# Quectel_M66.net
KiCad netlist of a schematic drawn in Altium Designer
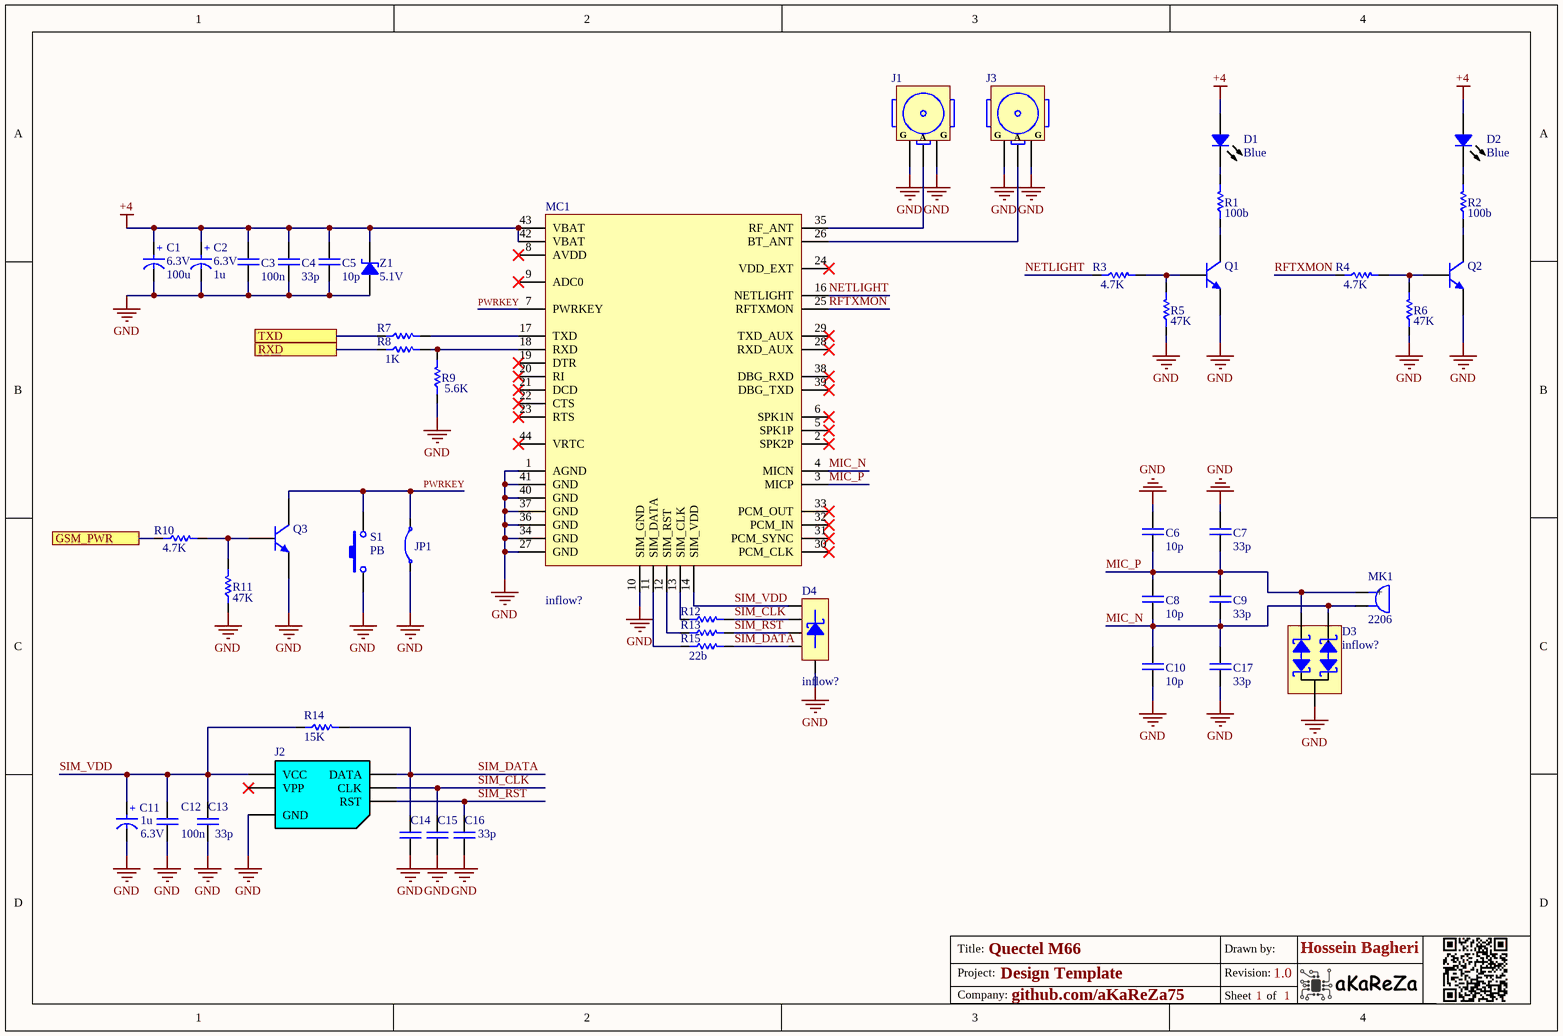
[diagram p0: Quectel M66.SchDoc]

(export (version "E")
  (design (tool "Eeschema 10.0.6"))
  (components
    (comp (ref "C1")
      (value "100u")
      (footprint "SMT_C_Tantalum_C")
      (description "Tantalum Capacitor,TAJ Series-SMD")
      (fields (field (name "RATING") "6.3V"))
      (libsource (lib "aKaReZa") (part "Cap_Tantalum"))
    )
    (comp (ref "C2")
      (value "1u")
      (footprint "SMT_C_Tantalum_A")
      (description "Tantalum Capacitor,TAJ Series-SMD")
      (fields (field (name "RATING") "6.3V"))
      (libsource (lib "aKaReZa") (part "Cap_Tantalum"))
    )
    (comp (ref "C3")
      (value "100n")
      (footprint "CAP 1206/3216")
      (description "Bipolar ceramic capacitor SMD")
      (libsource (lib "aKaReZa") (part "Cap_Multi_SMD_100nF_1206"))
    )
    (comp (ref "C4")
      (value "33p")
      (footprint "CAP 1206/3216")
      (description "Bipolar ceramic capacitor SMD")
      (libsource (lib "aKaReZa") (part "Cap_Multi_SMD_1206"))
    )
    (comp (ref "C5")
      (value "10p")
      (footprint "CAP 1206/3216")
      (description "Bipolar ceramic capacitor SMD")
      (libsource (lib "aKaReZa") (part "Cap_Multi_SMD_1206"))
    )
    (comp (ref "C6")
      (value "10p")
      (footprint "CAP 0603/1608")
      (description "Bipolar ceramic capacitor SMD")
      (fields (field (name "VALIDATION") "Valid"))
      (libsource (lib "aKaReZa") (part "Cap_Multi_SMD"))
    )
    (comp (ref "C7")
      (value "33p")
      (footprint "CAP 0603/1608")
      (description "Bipolar ceramic capacitor SMD")
      (fields (field (name "VALIDATION") "Valid"))
      (libsource (lib "aKaReZa") (part "Cap_Multi_SMD"))
    )
    (comp (ref "C8")
      (value "10p")
      (footprint "CAP 0603/1608")
      (description "Bipolar ceramic capacitor SMD")
      (fields (field (name "VALIDATION") "Valid"))
      (libsource (lib "aKaReZa") (part "Cap_Multi_SMD"))
    )
    (comp (ref "C9")
      (value "33p")
      (footprint "CAP 0603/1608")
      (description "Bipolar ceramic capacitor SMD")
      (fields (field (name "VALIDATION") "Valid"))
      (libsource (lib "aKaReZa") (part "Cap_Multi_SMD"))
    )
    (comp (ref "C10")
      (value "10p")
      (footprint "CAP 0603/1608")
      (description "Bipolar ceramic capacitor SMD")
      (fields (field (name "VALIDATION") "Valid"))
      (libsource (lib "aKaReZa") (part "Cap_Multi_SMD"))
    )
    (comp (ref "C11")
      (value "1u")
      (footprint "SMT_C_Tantalum_A")
      (description "Tantalum Capacitor,TAJ Series-SMD")
      (fields (field (name "RATING") "6.3V"))
      (libsource (lib "aKaReZa") (part "Cap_Tantalum"))
    )
    (comp (ref "C12")
      (value "100n")
      (footprint "CAP 0805/2012")
      (description "Bipolar ceramic capacitor SMD")
      (libsource (lib "aKaReZa") (part "Cap_Multi_SMD_100nF_0805"))
    )
    (comp (ref "C13")
      (value "33p")
      (footprint "CAP 0805/2012")
      (description "Bipolar ceramic capacitor SMD")
      (libsource (lib "aKaReZa") (part "Cap_Multi_SMD_0805"))
    )
    (comp (ref "C14")
      (value "33p")
      (footprint "CAP 0805/2012")
      (description "Bipolar ceramic capacitor SMD")
      (libsource (lib "aKaReZa") (part "Cap_Multi_SMD_0805"))
    )
    (comp (ref "C15")
      (value "33p")
      (footprint "CAP 0805/2012")
      (description "Bipolar ceramic capacitor SMD")
      (libsource (lib "aKaReZa") (part "Cap_Multi_SMD_0805"))
    )
    (comp (ref "C16")
      (value "33p")
      (footprint "CAP 0805/2012")
      (description "Bipolar ceramic capacitor SMD")
      (libsource (lib "aKaReZa") (part "Cap_Multi_SMD_0805"))
    )
    (comp (ref "C17")
      (value "33p")
      (footprint "CAP 0603/1608")
      (description "Bipolar ceramic capacitor SMD")
      (fields (field (name "VALIDATION") "Valid"))
      (libsource (lib "aKaReZa") (part "Cap_Multi_SMD"))
    )
    (comp (ref "D1")
      (value "Blue")
      (footprint "LED 0805/2012 BLUE")
      (description "LED")
      (fields (field (name "VALIDATION") "Valid"))
      (libsource (lib "aKaReZa") (part "Semi_LED_SMD"))
    )
    (comp (ref "D2")
      (value "Blue")
      (footprint "LED 0805/2012 BLUE")
      (description "LED")
      (fields (field (name "VALIDATION") "Valid"))
      (libsource (lib "aKaReZa") (part "Semi_LED_SMD"))
    )
    (comp (ref "D3")
      (value "SM712")
      (footprint "SOT23_M")
      (description "TVS, ESD PROTECT, 2CH, 400W/17A PP, 7.5VBR, ±8KV ESDmin")
      (fields (field (name "INFLOW") "inflow?") (field (name "VALIDATION") "Valid"))
      (libsource (lib "aKaReZa") (part "Semi_Diod_TVS_SM712"))
    )
    (comp (ref "D4")
      (value "SMF-05")
      (footprint "SC70-5_N")
      (description "TVS Diode Array")
      (fields (field (name "INFLOW") "inflow?") (field (name "VALIDATION") "Valid"))
      (libsource (lib "aKaReZa") (part "Semi_Diod_TVS_SMF05"))
    )
    (comp (ref "J1") (value "U.FL") (footprint "IPEX-3x3mm") (libsource (lib "aKaReZa") (part "Con_RF_U.FL")))
    (comp (ref "J2")
      (value "6'Pin")
      (footprint "GCT_SIM8051_Plastik")
      (description "Nano SimCard Holder 6P")
      (fields (field (name "VALIDATION") "Valid"))
      (libsource (lib "aKaReZa") (part "Con_Socket_SimCard_1"))
    )
    (comp (ref "J3") (value "U.FL") (footprint "IPEX-3x3mm") (libsource (lib "aKaReZa") (part "Con_RF_U.FL")))
    (comp (ref "JP1")
      (value "Jumper")
      (footprint "RESC2012M (0805)")
      (description "Jumper Component")
      (fields (field (name "VALIDATION") "Valid"))
      (libsource (lib "aKaReZa") (part "Other_Elec_Jumper_0805"))
    )
    (comp (ref "MC1")
      (value "M66")
      (footprint "m66")
      (description "Quectel GSM/GPRS Module")
      (fields (field (name "INFLOW") "inflow?") (field (name "VALIDATION") "Valid"))
      (libsource (lib "aKaReZa") (part "ModSen_Com_M66"))
    )
    (comp (ref "MK1")
      (value "Mic")
      (footprint "mic6")
      (description "Microphone")
      (fields (field (name "INFLOW") "2206") (field (name "VALIDATION") "NT"))
      (libsource (lib "aKaReZa") (part "Other_Elec_Microphone"))
    )
    (comp (ref "Q1")
      (value "NPN")
      (footprint "SOT23_N")
      (description "NPN General purpose Transistor")
      (fields (field (name "VALIDATION") "Valid"))
      (libsource (lib "aKaReZa") (part "Semi_BJT_BC817"))
    )
    (comp (ref "Q2")
      (value "NPN")
      (footprint "SOT23_N")
      (description "NPN General purpose Transistor")
      (fields (field (name "VALIDATION") "Valid"))
      (libsource (lib "aKaReZa") (part "Semi_BJT_BC817"))
    )
    (comp (ref "Q3")
      (value "NPN")
      (footprint "SOT23_N")
      (description "NPN General purpose Transistor")
      (fields (field (name "VALIDATION") "Valid"))
      (libsource (lib "aKaReZa") (part "Semi_BJT_BC817"))
    )
    (comp (ref "R1")
      (value "100b")
      (footprint "RES 0805 (2012X06L)")
      (description "Resistor")
      (libsource (lib "aKaReZa") (part "Res_SMD_0805"))
    )
    (comp (ref "R2")
      (value "100b")
      (footprint "RES 0805 (2012X06L)")
      (description "Resistor")
      (libsource (lib "aKaReZa") (part "Res_SMD_0805"))
    )
    (comp (ref "R3")
      (value "4.7K")
      (footprint "RES 0805 (2012X06L)")
      (description "Resistor")
      (libsource (lib "aKaReZa") (part "Res_SMD_0805"))
    )
    (comp (ref "R4")
      (value "4.7K")
      (footprint "RES 0805 (2012X06L)")
      (description "Resistor")
      (libsource (lib "aKaReZa") (part "Res_SMD_0805"))
    )
    (comp (ref "R5")
      (value "47K")
      (footprint "RES 0805 (2012X06L)")
      (description "Resistor")
      (libsource (lib "aKaReZa") (part "Res_SMD_0805"))
    )
    (comp (ref "R6")
      (value "47K")
      (footprint "RES 0805 (2012X06L)")
      (description "Resistor")
      (libsource (lib "aKaReZa") (part "Res_SMD_0805"))
    )
    (comp (ref "R7")
      (value "1K")
      (footprint "RES 0805 (2012X06L)")
      (description "Resistor")
      (libsource (lib "aKaReZa") (part "Res_SMD_0805"))
    )
    (comp (ref "R8")
      (value "1K")
      (footprint "RES 0805 (2012X06L)")
      (description "Resistor")
      (libsource (lib "aKaReZa") (part "Res_SMD_0805"))
    )
    (comp (ref "R9")
      (value "5.6K")
      (footprint "RES 0805 (2012X06L)")
      (description "Resistor")
      (libsource (lib "aKaReZa") (part "Res_SMD_0805"))
    )
    (comp (ref "R10")
      (value "4.7K")
      (footprint "RES 0805 (2012X06L)")
      (description "Resistor")
      (libsource (lib "aKaReZa") (part "Res_SMD_0805"))
    )
    (comp (ref "R11")
      (value "47K")
      (footprint "RES 0805 (2012X06L)")
      (description "Resistor")
      (libsource (lib "aKaReZa") (part "Res_SMD_0805"))
    )
    (comp (ref "R12")
      (value "22b")
      (footprint "RES 0805 (2012X06L)")
      (description "Resistor")
      (libsource (lib "aKaReZa") (part "Res_SMD_0805"))
    )
    (comp (ref "R13")
      (value "22b")
      (footprint "RES 0805 (2012X06L)")
      (description "Resistor")
      (libsource (lib "aKaReZa") (part "Res_SMD_0805"))
    )
    (comp (ref "R14")
      (value "15K")
      (footprint "RES 0805 (2012X06L)")
      (description "Resistor")
      (libsource (lib "aKaReZa") (part "Res_SMD_0805"))
    )
    (comp (ref "R15")
      (value "22b")
      (footprint "RES 0805 (2012X06L)")
      (description "Resistor")
      (libsource (lib "aKaReZa") (part "Res_SMD_0805"))
    )
    (comp (ref "S1")
      (value "PB")
      (footprint "SW_PB_SMD_2PIN_SPST_6X3X2")
      (description "SMT Tactile ‎Switch")
      (fields (field (name "VALIDATION") "Valid"))
      (libsource (lib "aKaReZa") (part "SW_PushButton_2_SMD"))
    )
    (comp (ref "Z1")
      (value "5.1V")
      (footprint "SOD80, LL-34")
      (description "Zener Diode")
      (libsource (lib "aKaReZa") (part "Semi_Diod_Zener_SMD"))
    )
  )
  (nets
    (net (code "1") (name "+4") (class "Default")
      (node (ref "C1") (pin "1") (pinfunction "+_1") (pintype "passive"))
      (node (ref "C2") (pin "1") (pinfunction "+_1") (pintype "passive"))
      (node (ref "C3") (pin "1") (pinfunction "1_1") (pintype "passive"))
      (node (ref "C4") (pin "1") (pinfunction "1_1") (pintype "passive"))
      (node (ref "C5") (pin "1") (pinfunction "1_1") (pintype "passive"))
      (node (ref "D1") (pin "1") (pinfunction "1_1") (pintype "passive"))
      (node (ref "D2") (pin "1") (pinfunction "1_1") (pintype "passive"))
      (node (ref "MC1") (pin "42") (pinfunction "VBAT_42") (pintype "passive"))
      (node (ref "MC1") (pin "43") (pinfunction "VBAT_43") (pintype "passive"))
      (node (ref "Z1") (pin "2") (pinfunction "2_2") (pintype "passive"))
    )
    (net (code "2") (name "/GSM_PWR") (class "Default")
      (node (ref "R10") (pin "1") (pinfunction "1_1") (pintype "passive"))
    )
    (net (code "3") (name "/MIC_N") (class "Default")
      (node (ref "C10") (pin "1") (pinfunction "1_1") (pintype "passive"))
      (node (ref "C17") (pin "1") (pinfunction "1_1") (pintype "passive"))
      (node (ref "C8") (pin "2") (pinfunction "2_2") (pintype "passive"))
      (node (ref "C9") (pin "2") (pinfunction "2_2") (pintype "passive"))
      (node (ref "D3") (pin "2") (pinfunction "2_2") (pintype "passive"))
      (node (ref "MC1") (pin "4") (pinfunction "MICN_4") (pintype "passive"))
      (node (ref "MK1") (pin "2") (pinfunction "2_2") (pintype "passive"))
    )
    (net (code "4") (name "/MIC_P") (class "Default")
      (node (ref "C6") (pin "2") (pinfunction "2_2") (pintype "passive"))
      (node (ref "C7") (pin "2") (pinfunction "2_2") (pintype "passive"))
      (node (ref "C8") (pin "1") (pinfunction "1_1") (pintype "passive"))
      (node (ref "C9") (pin "1") (pinfunction "1_1") (pintype "passive"))
      (node (ref "D3") (pin "1") (pinfunction "1_1") (pintype "passive"))
      (node (ref "MC1") (pin "3") (pinfunction "MICP_3") (pintype "passive"))
      (node (ref "MK1") (pin "1") (pinfunction "+_1") (pintype "passive"))
    )
    (net (code "5") (name "/NETLIGHT") (class "Default")
      (node (ref "MC1") (pin "16") (pinfunction "NETLIGHT_16") (pintype "passive"))
      (node (ref "R3") (pin "1") (pinfunction "1_1") (pintype "passive"))
    )
    (net (code "6") (name "/PWRKEY") (class "Default")
      (node (ref "JP1") (pin "2") (pinfunction "2_2") (pintype "passive"))
      (node (ref "MC1") (pin "7") (pinfunction "PWRKEY_7") (pintype "passive"))
      (node (ref "Q3") (pin "3") (pinfunction "C_3") (pintype "passive"))
      (node (ref "S1") (pin "2") (pinfunction "2_2") (pintype "passive"))
    )
    (net (code "7") (name "/RFTXMON") (class "Default")
      (node (ref "MC1") (pin "25") (pinfunction "RFTXMON_25") (pintype "passive"))
      (node (ref "R4") (pin "1") (pinfunction "1_1") (pintype "passive"))
    )
    (net (code "8") (name "/RXD") (class "Default")
      (node (ref "R8") (pin "1") (pinfunction "1_1") (pintype "passive"))
    )
    (net (code "9") (name "/SIM_CLK") (class "Default")
      (node (ref "C15") (pin "1") (pinfunction "1_1") (pintype "passive"))
      (node (ref "D4") (pin "4") (pinfunction "K_4") (pintype "passive"))
      (node (ref "J2") (pin "3") (pinfunction "CLK_3") (pintype "passive"))
      (node (ref "R12") (pin "2") (pinfunction "2_2") (pintype "passive"))
    )
    (net (code "10") (name "/SIM_DATA") (class "Default")
      (node (ref "C14") (pin "1") (pinfunction "1_1") (pintype "passive"))
      (node (ref "D4") (pin "5") (pinfunction "K_5") (pintype "passive"))
      (node (ref "J2") (pin "4") (pinfunction "DATA_4") (pintype "passive"))
      (node (ref "R14") (pin "2") (pinfunction "2_2") (pintype "passive"))
      (node (ref "R15") (pin "2") (pinfunction "2_2") (pintype "passive"))
    )
    (net (code "11") (name "/SIM_RST") (class "Default")
      (node (ref "C16") (pin "1") (pinfunction "1_1") (pintype "passive"))
      (node (ref "D4") (pin "1") (pinfunction "K_1") (pintype "passive"))
      (node (ref "J2") (pin "2") (pinfunction "RST_2") (pintype "passive"))
      (node (ref "R13") (pin "2") (pinfunction "2_2") (pintype "passive"))
    )
    (net (code "12") (name "/SIM_VDD") (class "Default")
      (node (ref "C11") (pin "1") (pinfunction "+_1") (pintype "passive"))
      (node (ref "C12") (pin "1") (pinfunction "1_1") (pintype "passive"))
      (node (ref "C13") (pin "1") (pinfunction "1_1") (pintype "passive"))
      (node (ref "D4") (pin "3") (pinfunction "K_3") (pintype "passive"))
      (node (ref "J2") (pin "1") (pinfunction "VCC_1") (pintype "passive"))
      (node (ref "MC1") (pin "14") (pinfunction "SIM_VDD_14") (pintype "passive"))
      (node (ref "R14") (pin "1") (pinfunction "1_1") (pintype "passive"))
    )
    (net (code "13") (name "/TXD") (class "Default")
      (node (ref "R7") (pin "1") (pinfunction "1_1") (pintype "passive"))
    )
    (net (code "14") (name "GND") (class "Default")
      (node (ref "C1") (pin "2") (pinfunction "-_2") (pintype "passive"))
      (node (ref "C10") (pin "2") (pinfunction "2_2") (pintype "passive"))
      (node (ref "C11") (pin "2") (pinfunction "-_2") (pintype "passive"))
      (node (ref "C12") (pin "2") (pinfunction "2_2") (pintype "passive"))
      (node (ref "C13") (pin "2") (pinfunction "2_2") (pintype "passive"))
      (node (ref "C14") (pin "2") (pinfunction "2_2") (pintype "passive"))
      (node (ref "C15") (pin "2") (pinfunction "2_2") (pintype "passive"))
      (node (ref "C16") (pin "2") (pinfunction "2_2") (pintype "passive"))
      (node (ref "C17") (pin "2") (pinfunction "2_2") (pintype "passive"))
      (node (ref "C2") (pin "2") (pinfunction "-_2") (pintype "passive"))
      (node (ref "C3") (pin "2") (pinfunction "2_2") (pintype "passive"))
      (node (ref "C4") (pin "2") (pinfunction "2_2") (pintype "passive"))
      (node (ref "C5") (pin "2") (pinfunction "2_2") (pintype "passive"))
      (node (ref "C6") (pin "1") (pinfunction "1_1") (pintype "passive"))
      (node (ref "C7") (pin "1") (pinfunction "1_1") (pintype "passive"))
      (node (ref "D3") (pin "3") (pinfunction "3_3") (pintype "passive"))
      (node (ref "D4") (pin "2") (pinfunction "K_2") (pintype "passive"))
      (node (ref "J1") (pin "2") (pinfunction "G_2") (pintype "passive"))
      (node (ref "J1") (pin "3") (pinfunction "G_3") (pintype "passive"))
      (node (ref "J2") (pin "5") (pinfunction "GND_5") (pintype "passive"))
      (node (ref "J3") (pin "2") (pinfunction "G_2") (pintype "passive"))
      (node (ref "J3") (pin "3") (pinfunction "G_3") (pintype "passive"))
      (node (ref "JP1") (pin "1") (pinfunction "1_1") (pintype "passive"))
      (node (ref "MC1") (pin "1") (pinfunction "AGND_1") (pintype "passive"))
      (node (ref "MC1") (pin "10") (pinfunction "SIM_GND_10") (pintype "passive"))
      (node (ref "MC1") (pin "27") (pinfunction "GND_27") (pintype "passive"))
      (node (ref "MC1") (pin "34") (pinfunction "GND_34") (pintype "passive"))
      (node (ref "MC1") (pin "36") (pinfunction "GND_36") (pintype "passive"))
      (node (ref "MC1") (pin "37") (pinfunction "GND_37") (pintype "passive"))
      (node (ref "MC1") (pin "40") (pinfunction "GND_40") (pintype "passive"))
      (node (ref "MC1") (pin "41") (pinfunction "GND_41") (pintype "passive"))
      (node (ref "Q1") (pin "2") (pinfunction "E_2") (pintype "passive"))
      (node (ref "Q2") (pin "2") (pinfunction "E_2") (pintype "passive"))
      (node (ref "Q3") (pin "2") (pinfunction "E_2") (pintype "passive"))
      (node (ref "R11") (pin "1") (pinfunction "1_1") (pintype "passive"))
      (node (ref "R5") (pin "1") (pinfunction "1_1") (pintype "passive"))
      (node (ref "R6") (pin "1") (pinfunction "1_1") (pintype "passive"))
      (node (ref "R9") (pin "1") (pinfunction "1_1") (pintype "passive"))
      (node (ref "S1") (pin "1") (pinfunction "1_1") (pintype "passive"))
      (node (ref "Z1") (pin "1") (pinfunction "1_1") (pintype "passive"))
    )
    (net (code "15") (name "Net-(D1-Pad2)") (class "Default")
      (node (ref "D1") (pin "2") (pinfunction "2_2") (pintype "passive"))
      (node (ref "R1") (pin "2") (pinfunction "2_2") (pintype "passive"))
    )
    (net (code "16") (name "Net-(D2-Pad2)") (class "Default")
      (node (ref "D2") (pin "2") (pinfunction "2_2") (pintype "passive"))
      (node (ref "R2") (pin "2") (pinfunction "2_2") (pintype "passive"))
    )
    (net (code "17") (name "Net-(J1-A)") (class "Default")
      (node (ref "J1") (pin "1") (pinfunction "A_1") (pintype "passive"))
      (node (ref "MC1") (pin "35") (pinfunction "RF_ANT_35") (pintype "passive"))
    )
    (net (code "18") (name "Net-(J3-A)") (class "Default")
      (node (ref "J3") (pin "1") (pinfunction "A_1") (pintype "passive"))
      (node (ref "MC1") (pin "26") (pinfunction "BT_ANT_26") (pintype "passive"))
    )
    (net (code "19") (name "Net-(MC1-RXD)") (class "Default")
      (node (ref "MC1") (pin "18") (pinfunction "RXD_18") (pintype "passive"))
      (node (ref "R8") (pin "2") (pinfunction "2_2") (pintype "passive"))
      (node (ref "R9") (pin "2") (pinfunction "2_2") (pintype "passive"))
    )
    (net (code "20") (name "Net-(MC1-SIM_CLK)") (class "Default")
      (node (ref "MC1") (pin "13") (pinfunction "SIM_CLK_13") (pintype "passive"))
      (node (ref "R12") (pin "1") (pinfunction "1_1") (pintype "passive"))
    )
    (net (code "21") (name "Net-(MC1-SIM_DATA)") (class "Default")
      (node (ref "MC1") (pin "11") (pinfunction "SIM_DATA_11") (pintype "passive"))
      (node (ref "R15") (pin "1") (pinfunction "1_1") (pintype "passive"))
    )
    (net (code "22") (name "Net-(MC1-SIM_RST)") (class "Default")
      (node (ref "MC1") (pin "12") (pinfunction "SIM_RST_12") (pintype "passive"))
      (node (ref "R13") (pin "1") (pinfunction "1_1") (pintype "passive"))
    )
    (net (code "23") (name "Net-(MC1-TXD)") (class "Default")
      (node (ref "MC1") (pin "17") (pinfunction "TXD_17") (pintype "passive"))
      (node (ref "R7") (pin "2") (pinfunction "2_2") (pintype "passive"))
    )
    (net (code "24") (name "Net-(Q1-B)") (class "Default")
      (node (ref "Q1") (pin "1") (pinfunction "B_1") (pintype "passive"))
      (node (ref "R3") (pin "2") (pinfunction "2_2") (pintype "passive"))
      (node (ref "R5") (pin "2") (pinfunction "2_2") (pintype "passive"))
    )
    (net (code "25") (name "Net-(Q1-C)") (class "Default")
      (node (ref "Q1") (pin "3") (pinfunction "C_3") (pintype "passive"))
      (node (ref "R1") (pin "1") (pinfunction "1_1") (pintype "passive"))
    )
    (net (code "26") (name "Net-(Q2-B)") (class "Default")
      (node (ref "Q2") (pin "1") (pinfunction "B_1") (pintype "passive"))
      (node (ref "R4") (pin "2") (pinfunction "2_2") (pintype "passive"))
      (node (ref "R6") (pin "2") (pinfunction "2_2") (pintype "passive"))
    )
    (net (code "27") (name "Net-(Q2-C)") (class "Default")
      (node (ref "Q2") (pin "3") (pinfunction "C_3") (pintype "passive"))
      (node (ref "R2") (pin "1") (pinfunction "1_1") (pintype "passive"))
    )
    (net (code "28") (name "Net-(Q3-B)") (class "Default")
      (node (ref "Q3") (pin "1") (pinfunction "B_1") (pintype "passive"))
      (node (ref "R10") (pin "2") (pinfunction "2_2") (pintype "passive"))
      (node (ref "R11") (pin "2") (pinfunction "2_2") (pintype "passive"))
    )
    (net (code "29") (name "unconnected-(J2-VPP-Pad6)") (class "Default")
      (node (ref "J2") (pin "6") (pinfunction "VPP_6") (pintype "passive+no_connect"))
    )
    (net (code "30") (name "unconnected-(MC1-ADC0-Pad9)") (class "Default")
      (node (ref "MC1") (pin "9") (pinfunction "ADC0_9") (pintype "passive+no_connect"))
    )
    (net (code "31") (name "unconnected-(MC1-AVDD-Pad8)") (class "Default")
      (node (ref "MC1") (pin "8") (pinfunction "AVDD_8") (pintype "passive+no_connect"))
    )
    (net (code "32") (name "unconnected-(MC1-CTS-Pad22)") (class "Default")
      (node (ref "MC1") (pin "22") (pinfunction "CTS_22") (pintype "passive+no_connect"))
    )
    (net (code "33") (name "unconnected-(MC1-DBG_RXD-Pad38)") (class "Default")
      (node (ref "MC1") (pin "38") (pinfunction "DBG_RXD_38") (pintype "passive+no_connect"))
    )
    (net (code "34") (name "unconnected-(MC1-DBG_TXD-Pad39)") (class "Default")
      (node (ref "MC1") (pin "39") (pinfunction "DBG_TXD_39") (pintype "passive+no_connect"))
    )
    (net (code "35") (name "unconnected-(MC1-DCD-Pad21)") (class "Default")
      (node (ref "MC1") (pin "21") (pinfunction "DCD_21") (pintype "passive+no_connect"))
    )
    (net (code "36") (name "unconnected-(MC1-DTR-Pad19)") (class "Default")
      (node (ref "MC1") (pin "19") (pinfunction "DTR_19") (pintype "passive+no_connect"))
    )
    (net (code "37") (name "unconnected-(MC1-PCM_CLK-Pad30)") (class "Default")
      (node (ref "MC1") (pin "30") (pinfunction "PCM_CLK_30") (pintype "passive+no_connect"))
    )
    (net (code "38") (name "unconnected-(MC1-PCM_IN-Pad32)") (class "Default")
      (node (ref "MC1") (pin "32") (pinfunction "PCM_IN_32") (pintype "passive+no_connect"))
    )
    (net (code "39") (name "unconnected-(MC1-PCM_OUT-Pad33)") (class "Default")
      (node (ref "MC1") (pin "33") (pinfunction "PCM_OUT_33") (pintype "passive+no_connect"))
    )
    (net (code "40") (name "unconnected-(MC1-PCM_SYNC-Pad31)") (class "Default")
      (node (ref "MC1") (pin "31") (pinfunction "PCM_SYNC_31") (pintype "passive+no_connect"))
    )
    (net (code "41") (name "unconnected-(MC1-RI-Pad20)") (class "Default")
      (node (ref "MC1") (pin "20") (pinfunction "RI_20") (pintype "passive+no_connect"))
    )
    (net (code "42") (name "unconnected-(MC1-RTS-Pad23)") (class "Default")
      (node (ref "MC1") (pin "23") (pinfunction "RTS_23") (pintype "passive+no_connect"))
    )
    (net (code "43") (name "unconnected-(MC1-RXD_AUX-Pad28)") (class "Default")
      (node (ref "MC1") (pin "28") (pinfunction "RXD_AUX_28") (pintype "passive+no_connect"))
    )
    (net (code "44") (name "unconnected-(MC1-SPK1N-Pad6)") (class "Default")
      (node (ref "MC1") (pin "6") (pinfunction "SPK1N_6") (pintype "passive+no_connect"))
    )
    (net (code "45") (name "unconnected-(MC1-SPK1P-Pad5)") (class "Default")
      (node (ref "MC1") (pin "5") (pinfunction "SPK1P_5") (pintype "passive+no_connect"))
    )
    (net (code "46") (name "unconnected-(MC1-SPK2P-Pad2)") (class "Default")
      (node (ref "MC1") (pin "2") (pinfunction "SPK2P_2") (pintype "passive+no_connect"))
    )
    (net (code "47") (name "unconnected-(MC1-TXD_AUX-Pad29)") (class "Default")
      (node (ref "MC1") (pin "29") (pinfunction "TXD_AUX_29") (pintype "passive+no_connect"))
    )
    (net (code "48") (name "unconnected-(MC1-VDD_EXT-Pad24)") (class "Default")
      (node (ref "MC1") (pin "24") (pinfunction "VDD_EXT_24") (pintype "passive+no_connect"))
    )
    (net (code "49") (name "unconnected-(MC1-VRTC-Pad44)") (class "Default")
      (node (ref "MC1") (pin "44") (pinfunction "VRTC_44") (pintype "passive+no_connect"))
    )
  )
)
